# mag_pos_prog.net
KiCad netlist of a schematic drawn in Altium Designer
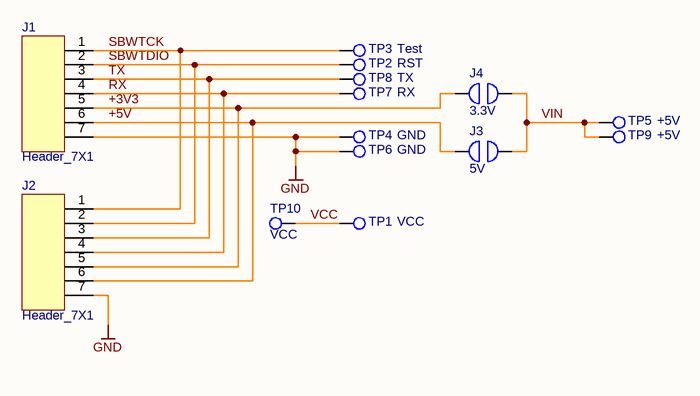
[diagram p0: mag_pos_prog.SchDoc]

(export (version "E")
  (design (tool "Eeschema 10.0.6"))
  (components
    (comp (ref "J1")
      (value "Header_7X1")
      (footprint "mag_pos:HDRV7W64P254_1X7_1778X254X800P")
      (description "Header 7x1 pins")
      (libsource (lib "mag_pos") (part "Header_7X1"))
    )
    (comp (ref "J2")
      (value "Header_7X1")
      (footprint "mag_pos:HDRV7W64P254_1X7_1778X254X800P")
      (description "Header 7x1 pins")
      (libsource (lib "mag_pos") (part "Header_7X1"))
    )
    (comp (ref "J3")
      (value "5V")
      (footprint "AHO_Altium_Lib:Solder_Jumper_2pin_0.2mm")
      (libsource (lib "AHO_Altium_Lib") (part "SolderJumper_2"))
    )
    (comp (ref "J4")
      (value "3.3V")
      (footprint "AHO_Altium_Lib:Solder_Jumper_2pin_0.2mm")
      (libsource (lib "AHO_Altium_Lib") (part "SolderJumper_2"))
    )
    (comp (ref "TP1")
      (value "VCC")
      (footprint "mag_pos:TP_SPRING_PROBE_1.7MM_2.5MM")
      (description "Spring probe sleeve 1.7mm hole diameter, 2.5mm pad size, Harwin S25-022")
      (libsource (lib "mag_pos") (part "TP_SPRING_PROBE_1.7MM"))
    )
    (comp (ref "TP2")
      (value "RST")
      (footprint "mag_pos:TP_SPRING_PROBE_1.7MM_2.5MM")
      (description "Spring probe sleeve 1.7mm hole diameter, 2.5mm pad size, Harwin S25-022")
      (libsource (lib "mag_pos") (part "TP_SPRING_PROBE_1.7MM"))
    )
    (comp (ref "TP3")
      (value "Test")
      (footprint "mag_pos:TP_SPRING_PROBE_1.7MM_2.5MM")
      (description "Spring probe sleeve 1.7mm hole diameter, 2.5mm pad size, Harwin S25-022")
      (libsource (lib "mag_pos") (part "TP_SPRING_PROBE_1.7MM"))
    )
    (comp (ref "TP4")
      (value "GND")
      (footprint "mag_pos:TP_SPRING_PROBE_1.7MM_2.5MM")
      (description "Spring probe sleeve 1.7mm hole diameter, 2.5mm pad size, Harwin S25-022")
      (libsource (lib "mag_pos") (part "TP_SPRING_PROBE_1.7MM"))
    )
    (comp (ref "TP5")
      (value "+5V")
      (footprint "mag_pos:TP_SPRING_PROBE_1.7MM_2.5MM")
      (description "Spring probe sleeve 1.7mm hole diameter, 2.5mm pad size, Harwin S25-022")
      (libsource (lib "mag_pos") (part "TP_SPRING_PROBE_1.7MM"))
    )
    (comp (ref "TP6")
      (value "GND")
      (footprint "mag_pos:TP_SPRING_PROBE_1.7MM_2.5MM")
      (description "Spring probe sleeve 1.7mm hole diameter, 2.5mm pad size, Harwin S25-022")
      (libsource (lib "mag_pos") (part "TP_SPRING_PROBE_1.7MM"))
    )
    (comp (ref "TP7")
      (value "RX")
      (footprint "mag_pos:TP_SPRING_PROBE_1.7MM_2.5MM")
      (description "Spring probe sleeve 1.7mm hole diameter, 2.5mm pad size, Harwin S25-022")
      (libsource (lib "mag_pos") (part "TP_SPRING_PROBE_1.7MM"))
    )
    (comp (ref "TP8")
      (value "TX")
      (footprint "mag_pos:TP_SPRING_PROBE_1.7MM_2.5MM")
      (description "Spring probe sleeve 1.7mm hole diameter, 2.5mm pad size, Harwin S25-022")
      (libsource (lib "mag_pos") (part "TP_SPRING_PROBE_1.7MM"))
    )
    (comp (ref "TP9")
      (value "+5V")
      (footprint "mag_pos:TP_SPRING_PROBE_1.7MM_2.5MM")
      (description "Spring probe sleeve 1.7mm hole diameter, 2.5mm pad size, Harwin S25-022")
      (libsource (lib "mag_pos") (part "TP_SPRING_PROBE_1.7MM"))
    )
    (comp (ref "TP10")
      (value "VCC")
      (footprint "mag_pos:TP_SMD_1MM")
      (description "Testpoint SMD 1mm")
      (libsource (lib "mag_pos") (part "TP_SMD_1mm"))
    )
  )
  (nets
    (net (code "1") (name "/+3V3") (class "Default")
      (node (ref "J1") (pin "5") (pinfunction "5_5") (pintype "passive"))
      (node (ref "J2") (pin "5") (pinfunction "5_5") (pintype "passive"))
      (node (ref "J4") (pin "1") (pinfunction "1_1") (pintype "passive"))
    )
    (net (code "2") (name "/+5V") (class "Default")
      (node (ref "J1") (pin "6") (pinfunction "6_6") (pintype "passive"))
      (node (ref "J2") (pin "6") (pinfunction "6_6") (pintype "passive"))
      (node (ref "J3") (pin "1") (pinfunction "1_1") (pintype "passive"))
    )
    (net (code "3") (name "/RX") (class "Default")
      (node (ref "J1") (pin "4") (pinfunction "4_4") (pintype "passive"))
      (node (ref "J2") (pin "4") (pinfunction "4_4") (pintype "passive"))
      (node (ref "TP7") (pin "1") (pinfunction "1_1") (pintype "passive"))
    )
    (net (code "4") (name "/SBWTCK") (class "Default")
      (node (ref "J1") (pin "1") (pinfunction "1_1") (pintype "passive"))
      (node (ref "J2") (pin "1") (pinfunction "1_1") (pintype "passive"))
      (node (ref "TP3") (pin "1") (pinfunction "1_1") (pintype "passive"))
    )
    (net (code "5") (name "/SBWTDIO") (class "Default")
      (node (ref "J1") (pin "2") (pinfunction "2_2") (pintype "passive"))
      (node (ref "J2") (pin "2") (pinfunction "2_2") (pintype "passive"))
      (node (ref "TP2") (pin "1") (pinfunction "1_1") (pintype "passive"))
    )
    (net (code "6") (name "/TX") (class "Default")
      (node (ref "J1") (pin "3") (pinfunction "3_3") (pintype "passive"))
      (node (ref "J2") (pin "3") (pinfunction "3_3") (pintype "passive"))
      (node (ref "TP8") (pin "1") (pinfunction "1_1") (pintype "passive"))
    )
    (net (code "7") (name "/VCC") (class "Default")
      (node (ref "TP1") (pin "1") (pinfunction "1_1") (pintype "passive"))
      (node (ref "TP10") (pin "1") (pinfunction "1_1") (pintype "passive"))
    )
    (net (code "8") (name "/VIN") (class "Default")
      (node (ref "J3") (pin "2") (pinfunction "2_2") (pintype "passive"))
      (node (ref "J4") (pin "2") (pinfunction "2_2") (pintype "passive"))
      (node (ref "TP5") (pin "1") (pinfunction "1_1") (pintype "passive"))
      (node (ref "TP9") (pin "1") (pinfunction "1_1") (pintype "passive"))
    )
    (net (code "9") (name "GND") (class "Default")
      (node (ref "J1") (pin "7") (pinfunction "7_7") (pintype "passive"))
      (node (ref "J2") (pin "7") (pinfunction "7_7") (pintype "passive"))
      (node (ref "TP4") (pin "1") (pinfunction "1_1") (pintype "passive"))
      (node (ref "TP6") (pin "1") (pinfunction "1_1") (pintype "passive"))
    )
  )
)
